# Center_Console_-_Buttons_Interface.net
KiCad netlist of a schematic drawn in Altium Designer
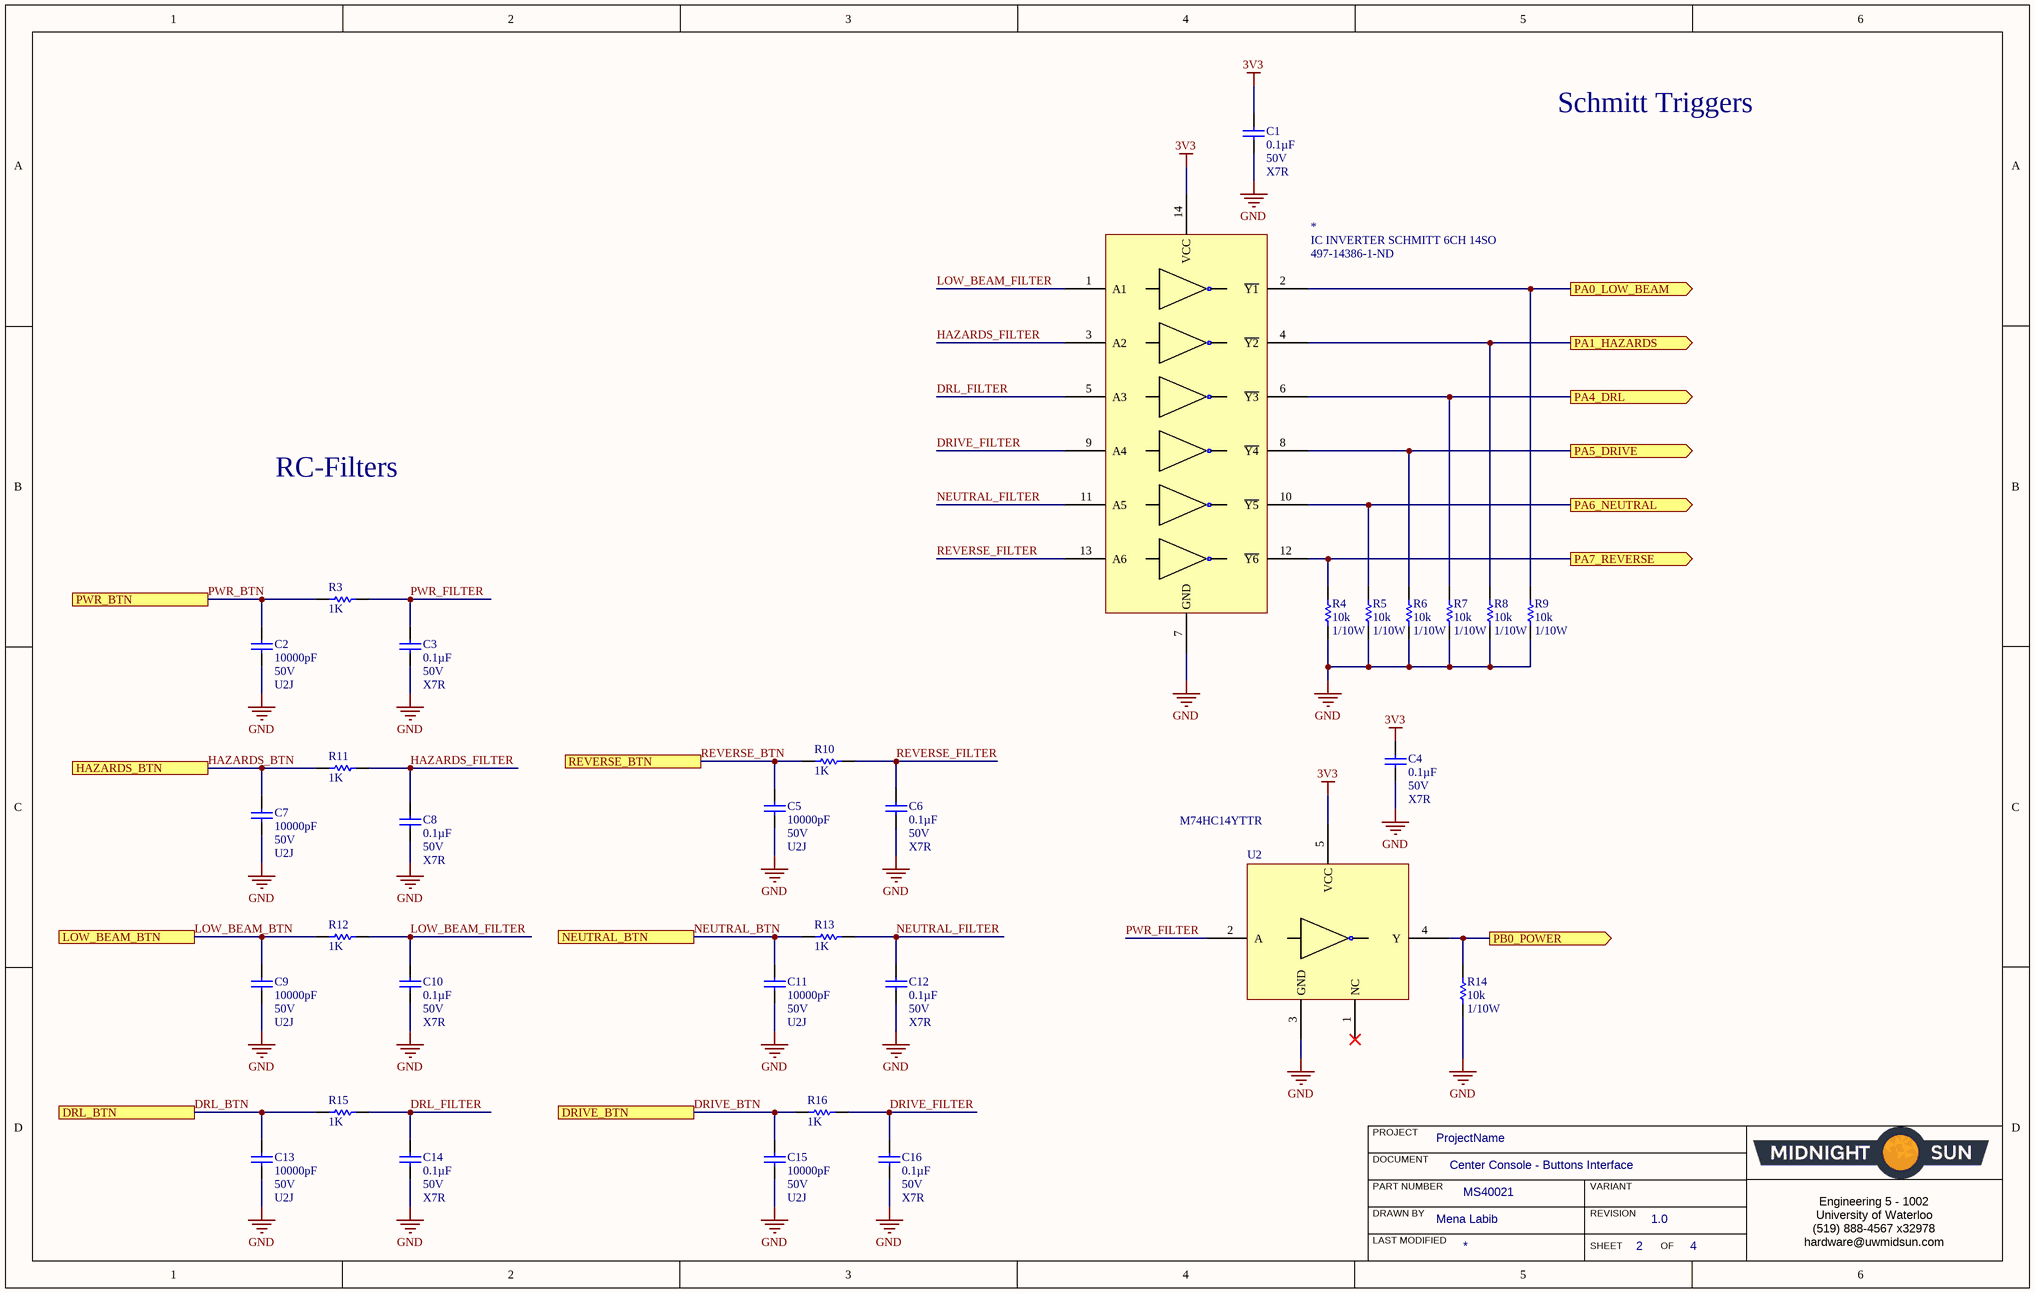
[diagram p0: Center Console - Buttons Interface.SchDoc]

(export (version "E")
  (design (tool "Eeschema 10.0.6"))
  (components
    (comp (ref "*")
      (value "IC INVERTER SCHMITT 6CH 14SO")
      (footprint "IC INVERTER SCHMITT 6CH 14TSO")
      (description "Inverter IC 6 Channel Schmitt Trigger 14-SO")
      (fields
        (field (name "MANUFACTURER") "STMicroelectronics")
        (field (name "MANUFACTURER PART NUMBER") "M74HC14YTTR")
        (field (name "SUPPLIER PART NUMBER 1") "497-14386-1-ND")
      )
      (libsource (lib "Schematic Diagrams") (part "IC INVERTER SCHMITT 6CH 14SO"))
    )
    (comp (ref "C1")
      (value "CAP CER 0.1UF 50V 10% X7R 0603")
      (footprint "CAP, 0603")
      (description "0.10µF ±10% 50V Ceramic Capacitor X7R 0603 (1608 Metric)")
      (fields
        (field (name "TOLERANCE") "±10%")
        (field (name "CAPACITANCE") "0.1µF")
        (field (name "VOLTAGE") "50V")
        (field (name "TEMPERATURE COEFFICIENT") "X7R")
      )
      (libsource (lib "Schematic Diagrams") (part "CAP CER 0.1UF 50V 10% X7R 0603"))
    )
    (comp (ref "C2")
      (value "CAP CER 10nF 50V 5% X7R 0603")
      (footprint "CAP, 0603")
      (description "10000pF ±5% 50V Ceramic Capacitor U2J 0603 (1608 Metric)")
      (fields
        (field (name "TOLERANCE") "±5%")
        (field (name "CAPACITANCE") "10000pF")
        (field (name "VOLTAGE") "50V")
        (field (name "TEMPERATURE COEFFICIENT") "U2J")
      )
      (libsource (lib "altium-import") (part "root_0_CAP CER 10nF 50V 5% X7R 0603_"))
    )
    (comp (ref "C3")
      (value "CAP CER 0.1UF 50V 10% X7R 0603")
      (footprint "CAP, 0603")
      (description "0.10µF ±10% 50V Ceramic Capacitor X7R 0603 (1608 Metric)")
      (fields
        (field (name "TOLERANCE") "±10%")
        (field (name "CAPACITANCE") "0.1µF")
        (field (name "VOLTAGE") "50V")
        (field (name "TEMPERATURE COEFFICIENT") "X7R")
      )
      (libsource (lib "Schematic Diagrams") (part "CAP CER 0.1UF 50V 10% X7R 0603"))
    )
    (comp (ref "C4")
      (value "CAP CER 0.1UF 50V 10% X7R 0603")
      (footprint "CAP, 0603")
      (description "0.10µF ±10% 50V Ceramic Capacitor X7R 0603 (1608 Metric)")
      (fields
        (field (name "TOLERANCE") "±10%")
        (field (name "CAPACITANCE") "0.1µF")
        (field (name "VOLTAGE") "50V")
        (field (name "TEMPERATURE COEFFICIENT") "X7R")
      )
      (libsource (lib "Schematic Diagrams") (part "CAP CER 0.1UF 50V 10% X7R 0603"))
    )
    (comp (ref "C5")
      (value "CAP CER 10nF 50V 5% X7R 0603")
      (footprint "CAP, 0603")
      (description "10000pF ±5% 50V Ceramic Capacitor U2J 0603 (1608 Metric)")
      (fields
        (field (name "TOLERANCE") "±5%")
        (field (name "CAPACITANCE") "10000pF")
        (field (name "VOLTAGE") "50V")
        (field (name "TEMPERATURE COEFFICIENT") "U2J")
      )
      (libsource (lib "altium-import") (part "root_0_CAP CER 10nF 50V 5% X7R 0603_"))
    )
    (comp (ref "C6")
      (value "CAP CER 0.1UF 50V 10% X7R 0603")
      (footprint "CAP, 0603")
      (description "0.10µF ±10% 50V Ceramic Capacitor X7R 0603 (1608 Metric)")
      (fields
        (field (name "TOLERANCE") "±10%")
        (field (name "CAPACITANCE") "0.1µF")
        (field (name "VOLTAGE") "50V")
        (field (name "TEMPERATURE COEFFICIENT") "X7R")
      )
      (libsource (lib "Schematic Diagrams") (part "CAP CER 0.1UF 50V 10% X7R 0603"))
    )
    (comp (ref "C7")
      (value "CAP CER 10nF 50V 5% X7R 0603")
      (footprint "CAP, 0603")
      (description "10000pF ±5% 50V Ceramic Capacitor U2J 0603 (1608 Metric)")
      (fields
        (field (name "TOLERANCE") "±5%")
        (field (name "CAPACITANCE") "10000pF")
        (field (name "VOLTAGE") "50V")
        (field (name "TEMPERATURE COEFFICIENT") "U2J")
      )
      (libsource (lib "altium-import") (part "root_0_CAP CER 10nF 50V 5% X7R 0603_"))
    )
    (comp (ref "C8")
      (value "CAP CER 0.1UF 50V 10% X7R 0603")
      (footprint "CAP, 0603")
      (description "0.10µF ±10% 50V Ceramic Capacitor X7R 0603 (1608 Metric)")
      (fields
        (field (name "TOLERANCE") "±10%")
        (field (name "CAPACITANCE") "0.1µF")
        (field (name "VOLTAGE") "50V")
        (field (name "TEMPERATURE COEFFICIENT") "X7R")
      )
      (libsource (lib "Schematic Diagrams") (part "CAP CER 0.1UF 50V 10% X7R 0603"))
    )
    (comp (ref "C9")
      (value "CAP CER 10nF 50V 5% X7R 0603")
      (footprint "CAP, 0603")
      (description "10000pF ±5% 50V Ceramic Capacitor U2J 0603 (1608 Metric)")
      (fields
        (field (name "TOLERANCE") "±5%")
        (field (name "CAPACITANCE") "10000pF")
        (field (name "VOLTAGE") "50V")
        (field (name "TEMPERATURE COEFFICIENT") "U2J")
      )
      (libsource (lib "altium-import") (part "root_0_CAP CER 10nF 50V 5% X7R 0603_"))
    )
    (comp (ref "C10")
      (value "CAP CER 0.1UF 50V 10% X7R 0603")
      (footprint "CAP, 0603")
      (description "0.10µF ±10% 50V Ceramic Capacitor X7R 0603 (1608 Metric)")
      (fields
        (field (name "TOLERANCE") "±10%")
        (field (name "CAPACITANCE") "0.1µF")
        (field (name "VOLTAGE") "50V")
        (field (name "TEMPERATURE COEFFICIENT") "X7R")
      )
      (libsource (lib "Schematic Diagrams") (part "CAP CER 0.1UF 50V 10% X7R 0603"))
    )
    (comp (ref "C11")
      (value "CAP CER 10nF 50V 5% X7R 0603")
      (footprint "CAP, 0603")
      (description "10000pF ±5% 50V Ceramic Capacitor U2J 0603 (1608 Metric)")
      (fields
        (field (name "TOLERANCE") "±5%")
        (field (name "CAPACITANCE") "10000pF")
        (field (name "VOLTAGE") "50V")
        (field (name "TEMPERATURE COEFFICIENT") "U2J")
      )
      (libsource (lib "altium-import") (part "root_0_CAP CER 10nF 50V 5% X7R 0603_"))
    )
    (comp (ref "C12")
      (value "CAP CER 0.1UF 50V 10% X7R 0603")
      (footprint "CAP, 0603")
      (description "0.10µF ±10% 50V Ceramic Capacitor X7R 0603 (1608 Metric)")
      (fields
        (field (name "TOLERANCE") "±10%")
        (field (name "CAPACITANCE") "0.1µF")
        (field (name "VOLTAGE") "50V")
        (field (name "TEMPERATURE COEFFICIENT") "X7R")
      )
      (libsource (lib "Schematic Diagrams") (part "CAP CER 0.1UF 50V 10% X7R 0603"))
    )
    (comp (ref "C13")
      (value "CAP CER 10nF 50V 5% X7R 0603")
      (footprint "CAP, 0603")
      (description "10000pF ±5% 50V Ceramic Capacitor U2J 0603 (1608 Metric)")
      (fields
        (field (name "TOLERANCE") "±5%")
        (field (name "CAPACITANCE") "10000pF")
        (field (name "VOLTAGE") "50V")
        (field (name "TEMPERATURE COEFFICIENT") "U2J")
      )
      (libsource (lib "altium-import") (part "root_0_CAP CER 10nF 50V 5% X7R 0603_"))
    )
    (comp (ref "C14")
      (value "CAP CER 0.1UF 50V 10% X7R 0603")
      (footprint "CAP, 0603")
      (description "0.10µF ±10% 50V Ceramic Capacitor X7R 0603 (1608 Metric)")
      (fields
        (field (name "TOLERANCE") "±10%")
        (field (name "CAPACITANCE") "0.1µF")
        (field (name "VOLTAGE") "50V")
        (field (name "TEMPERATURE COEFFICIENT") "X7R")
      )
      (libsource (lib "Schematic Diagrams") (part "CAP CER 0.1UF 50V 10% X7R 0603"))
    )
    (comp (ref "C15")
      (value "CAP CER 10nF 50V 5% X7R 0603")
      (footprint "CAP, 0603")
      (description "10000pF ±5% 50V Ceramic Capacitor U2J 0603 (1608 Metric)")
      (fields
        (field (name "TOLERANCE") "±5%")
        (field (name "CAPACITANCE") "10000pF")
        (field (name "VOLTAGE") "50V")
        (field (name "TEMPERATURE COEFFICIENT") "U2J")
      )
      (libsource (lib "altium-import") (part "root_0_CAP CER 10nF 50V 5% X7R 0603_"))
    )
    (comp (ref "C16")
      (value "CAP CER 0.1UF 50V 10% X7R 0603")
      (footprint "CAP, 0603")
      (description "0.10µF ±10% 50V Ceramic Capacitor X7R 0603 (1608 Metric)")
      (fields
        (field (name "TOLERANCE") "±10%")
        (field (name "CAPACITANCE") "0.1µF")
        (field (name "VOLTAGE") "50V")
        (field (name "TEMPERATURE COEFFICIENT") "X7R")
      )
      (libsource (lib "Schematic Diagrams") (part "CAP CER 0.1UF 50V 10% X7R 0603"))
    )
    (comp (ref "R3")
      (value "1K")
      (footprint "RES, 0603")
      (description "1k Ohm ±5% 0.1W, 1/10W Chip Resistor 0603 (1608 Metric)")
      (fields
        (field (name "MANUFACTURER") "Yageo")
        (field (name "MANUFACTURER PART NUMBER") "RC0603JR-071KL")
      )
      (libsource (lib "Schematic Diagrams") (part "RES 1K OHM 5% 1/10W 0603"))
    )
    (comp (ref "R4")
      (value "RES 10K OHM 1% 1/10W 0603")
      (footprint "RES, 0603")
      (description "RES SMD 10K OHM 1% 1/10W 0603")
      (fields
        (field (name "TOLERANCE") "±1%")
        (field (name "RESISTANCE") "10k")
        (field (name "POWER") "1/10W")
      )
      (libsource (lib "altium-import") (part "root_0_RES 10K OHM 1% 1/10W 0603_"))
    )
    (comp (ref "R5")
      (value "RES 10K OHM 1% 1/10W 0603")
      (footprint "RES, 0603")
      (description "RES SMD 10K OHM 1% 1/10W 0603")
      (fields
        (field (name "TOLERANCE") "±1%")
        (field (name "RESISTANCE") "10k")
        (field (name "POWER") "1/10W")
      )
      (libsource (lib "altium-import") (part "root_0_RES 10K OHM 1% 1/10W 0603_"))
    )
    (comp (ref "R6")
      (value "RES 10K OHM 1% 1/10W 0603")
      (footprint "RES, 0603")
      (description "RES SMD 10K OHM 1% 1/10W 0603")
      (fields
        (field (name "TOLERANCE") "±1%")
        (field (name "RESISTANCE") "10k")
        (field (name "POWER") "1/10W")
      )
      (libsource (lib "altium-import") (part "root_0_RES 10K OHM 1% 1/10W 0603_"))
    )
    (comp (ref "R7")
      (value "RES 10K OHM 1% 1/10W 0603")
      (footprint "RES, 0603")
      (description "RES SMD 10K OHM 1% 1/10W 0603")
      (fields
        (field (name "TOLERANCE") "±1%")
        (field (name "RESISTANCE") "10k")
        (field (name "POWER") "1/10W")
      )
      (libsource (lib "altium-import") (part "root_0_RES 10K OHM 1% 1/10W 0603_"))
    )
    (comp (ref "R8")
      (value "RES 10K OHM 1% 1/10W 0603")
      (footprint "RES, 0603")
      (description "RES SMD 10K OHM 1% 1/10W 0603")
      (fields
        (field (name "TOLERANCE") "±1%")
        (field (name "RESISTANCE") "10k")
        (field (name "POWER") "1/10W")
      )
      (libsource (lib "altium-import") (part "root_0_RES 10K OHM 1% 1/10W 0603_"))
    )
    (comp (ref "R9")
      (value "RES 10K OHM 1% 1/10W 0603")
      (footprint "RES, 0603")
      (description "RES SMD 10K OHM 1% 1/10W 0603")
      (fields
        (field (name "TOLERANCE") "±1%")
        (field (name "RESISTANCE") "10k")
        (field (name "POWER") "1/10W")
      )
      (libsource (lib "altium-import") (part "root_0_RES 10K OHM 1% 1/10W 0603_"))
    )
    (comp (ref "R10")
      (value "1K")
      (footprint "RES, 0603")
      (description "1k Ohm ±5% 0.1W, 1/10W Chip Resistor 0603 (1608 Metric)")
      (fields
        (field (name "MANUFACTURER") "Yageo")
        (field (name "MANUFACTURER PART NUMBER") "RC0603JR-071KL")
      )
      (libsource (lib "Schematic Diagrams") (part "RES 1K OHM 5% 1/10W 0603"))
    )
    (comp (ref "R11")
      (value "1K")
      (footprint "RES, 0603")
      (description "1k Ohm ±5% 0.1W, 1/10W Chip Resistor 0603 (1608 Metric)")
      (fields
        (field (name "MANUFACTURER") "Yageo")
        (field (name "MANUFACTURER PART NUMBER") "RC0603JR-071KL")
      )
      (libsource (lib "Schematic Diagrams") (part "RES 1K OHM 5% 1/10W 0603"))
    )
    (comp (ref "R12")
      (value "1K")
      (footprint "RES, 0603")
      (description "1k Ohm ±5% 0.1W, 1/10W Chip Resistor 0603 (1608 Metric)")
      (fields
        (field (name "MANUFACTURER") "Yageo")
        (field (name "MANUFACTURER PART NUMBER") "RC0603JR-071KL")
      )
      (libsource (lib "Schematic Diagrams") (part "RES 1K OHM 5% 1/10W 0603"))
    )
    (comp (ref "R13")
      (value "1K")
      (footprint "RES, 0603")
      (description "1k Ohm ±5% 0.1W, 1/10W Chip Resistor 0603 (1608 Metric)")
      (fields
        (field (name "MANUFACTURER") "Yageo")
        (field (name "MANUFACTURER PART NUMBER") "RC0603JR-071KL")
      )
      (libsource (lib "Schematic Diagrams") (part "RES 1K OHM 5% 1/10W 0603"))
    )
    (comp (ref "R14")
      (value "RES 10K OHM 1% 1/10W 0603")
      (footprint "RES, 0603")
      (description "RES SMD 10K OHM 1% 1/10W 0603")
      (fields
        (field (name "TOLERANCE") "±1%")
        (field (name "RESISTANCE") "10k")
        (field (name "POWER") "1/10W")
      )
      (libsource (lib "altium-import") (part "root_0_RES 10K OHM 1% 1/10W 0603_"))
    )
    (comp (ref "R15")
      (value "1K")
      (footprint "RES, 0603")
      (description "1k Ohm ±5% 0.1W, 1/10W Chip Resistor 0603 (1608 Metric)")
      (fields
        (field (name "MANUFACTURER") "Yageo")
        (field (name "MANUFACTURER PART NUMBER") "RC0603JR-071KL")
      )
      (libsource (lib "Schematic Diagrams") (part "RES 1K OHM 5% 1/10W 0603"))
    )
    (comp (ref "R16")
      (value "1K")
      (footprint "RES, 0603")
      (description "1k Ohm ±5% 0.1W, 1/10W Chip Resistor 0603 (1608 Metric)")
      (fields
        (field (name "MANUFACTURER") "Yageo")
        (field (name "MANUFACTURER PART NUMBER") "RC0603JR-071KL")
      )
      (libsource (lib "Schematic Diagrams") (part "RES 1K OHM 5% 1/10W 0603"))
    )
    (comp (ref "U2")
      (value "IC INVERTER SCHMITT 1CH SC70-5")
      (footprint "IC INVERTER SCHMITT 1CH SC70-5")
      (description "Inverter IC 1 Channel Schmitt Trigger SC-70-5")
      (fields
        (field (name "MANUFACTURER") "STMicroelectronics")
        (field (name "MANUFACTURER PART NUMBER") "M74HC14YTTR")
      )
      (libsource (lib "Schematic Diagrams") (part "IC INVERTER SCHMITT 1CH SC70-5"))
    )
  )
  (nets
    (net (code "1") (name "/DRIVE_BTN") (class "Default")
      (node (ref "C15") (pin "1") (pinfunction "1_1") (pintype "passive"))
      (node (ref "R16") (pin "1") (pinfunction "1_1") (pintype "passive"))
    )
    (net (code "2") (name "/DRIVE_FILTER") (class "Default")
      (node (ref "*") (pin "9") (pinfunction "A4_9") (pintype "passive"))
      (node (ref "C16") (pin "1") (pinfunction "1_1") (pintype "passive"))
      (node (ref "R16") (pin "2") (pinfunction "2_2") (pintype "passive"))
    )
    (net (code "3") (name "/DRL_BTN") (class "Default")
      (node (ref "C13") (pin "1") (pinfunction "1_1") (pintype "passive"))
      (node (ref "R15") (pin "1") (pinfunction "1_1") (pintype "passive"))
    )
    (net (code "4") (name "/DRL_FILTER") (class "Default")
      (node (ref "*") (pin "5") (pinfunction "A3_5") (pintype "passive"))
      (node (ref "C14") (pin "1") (pinfunction "1_1") (pintype "passive"))
      (node (ref "R15") (pin "2") (pinfunction "2_2") (pintype "passive"))
    )
    (net (code "5") (name "/HAZARDS_BTN") (class "Default")
      (node (ref "C7") (pin "1") (pinfunction "1_1") (pintype "passive"))
      (node (ref "R11") (pin "1") (pinfunction "1_1") (pintype "passive"))
    )
    (net (code "6") (name "/HAZARDS_FILTER") (class "Default")
      (node (ref "*") (pin "3") (pinfunction "A2_3") (pintype "passive"))
      (node (ref "C8") (pin "1") (pinfunction "1_1") (pintype "passive"))
      (node (ref "R11") (pin "2") (pinfunction "2_2") (pintype "passive"))
    )
    (net (code "7") (name "/LOW_BEAM_BTN") (class "Default")
      (node (ref "C9") (pin "1") (pinfunction "1_1") (pintype "passive"))
      (node (ref "R12") (pin "1") (pinfunction "1_1") (pintype "passive"))
    )
    (net (code "8") (name "/LOW_BEAM_FILTER") (class "Default")
      (node (ref "*") (pin "1") (pinfunction "A1_1") (pintype "passive"))
      (node (ref "C10") (pin "1") (pinfunction "1_1") (pintype "passive"))
      (node (ref "R12") (pin "2") (pinfunction "2_2") (pintype "passive"))
    )
    (net (code "9") (name "/NEUTRAL_BTN") (class "Default")
      (node (ref "C11") (pin "1") (pinfunction "1_1") (pintype "passive"))
      (node (ref "R13") (pin "1") (pinfunction "1_1") (pintype "passive"))
    )
    (net (code "10") (name "/NEUTRAL_FILTER") (class "Default")
      (node (ref "*") (pin "11") (pinfunction "A5_11") (pintype "passive"))
      (node (ref "C12") (pin "1") (pinfunction "1_1") (pintype "passive"))
      (node (ref "R13") (pin "2") (pinfunction "2_2") (pintype "passive"))
    )
    (net (code "11") (name "/PA0_LOW_BEAM") (class "Default")
      (node (ref "*") (pin "2") (pinfunction "~{Y1}_2") (pintype "passive"))
      (node (ref "R9") (pin "1") (pinfunction "1_1") (pintype "passive"))
    )
    (net (code "12") (name "/PA1_HAZARDS") (class "Default")
      (node (ref "*") (pin "4") (pinfunction "~{Y2}_4") (pintype "passive"))
      (node (ref "R8") (pin "1") (pinfunction "1_1") (pintype "passive"))
    )
    (net (code "13") (name "/PA4_DRL") (class "Default")
      (node (ref "*") (pin "6") (pinfunction "~{Y3}_6") (pintype "passive"))
      (node (ref "R7") (pin "1") (pinfunction "1_1") (pintype "passive"))
    )
    (net (code "14") (name "/PA5_DRIVE") (class "Default")
      (node (ref "*") (pin "8") (pinfunction "~{Y4}_8") (pintype "passive"))
      (node (ref "R6") (pin "1") (pinfunction "1_1") (pintype "passive"))
    )
    (net (code "15") (name "/PA6_NEUTRAL") (class "Default")
      (node (ref "*") (pin "10") (pinfunction "~{Y5}_10") (pintype "passive"))
      (node (ref "R5") (pin "1") (pinfunction "1_1") (pintype "passive"))
    )
    (net (code "16") (name "/PA7_REVERSE") (class "Default")
      (node (ref "*") (pin "12") (pinfunction "~{Y6}_12") (pintype "passive"))
      (node (ref "R4") (pin "1") (pinfunction "1_1") (pintype "passive"))
    )
    (net (code "17") (name "/PB0_POWER") (class "Default")
      (node (ref "R14") (pin "1") (pinfunction "1_1") (pintype "passive"))
      (node (ref "U2") (pin "4") (pinfunction "Y_4") (pintype "passive"))
    )
    (net (code "18") (name "/PWR_BTN") (class "Default")
      (node (ref "C2") (pin "1") (pinfunction "1_1") (pintype "passive"))
      (node (ref "R3") (pin "1") (pinfunction "1_1") (pintype "passive"))
    )
    (net (code "19") (name "/PWR_FILTER") (class "Default")
      (node (ref "C3") (pin "1") (pinfunction "1_1") (pintype "passive"))
      (node (ref "R3") (pin "2") (pinfunction "2_2") (pintype "passive"))
      (node (ref "U2") (pin "2") (pinfunction "A_2") (pintype "passive"))
    )
    (net (code "20") (name "/REVERSE_BTN") (class "Default")
      (node (ref "C5") (pin "1") (pinfunction "1_1") (pintype "passive"))
      (node (ref "R10") (pin "1") (pinfunction "1_1") (pintype "passive"))
    )
    (net (code "21") (name "/REVERSE_FILTER") (class "Default")
      (node (ref "*") (pin "13") (pinfunction "A6_13") (pintype "passive"))
      (node (ref "C6") (pin "1") (pinfunction "1_1") (pintype "passive"))
      (node (ref "R10") (pin "2") (pinfunction "2_2") (pintype "passive"))
    )
    (net (code "22") (name "3V3") (class "Default")
      (node (ref "*") (pin "14") (pinfunction "VCC_14") (pintype "passive"))
      (node (ref "C1") (pin "1") (pinfunction "1_1") (pintype "passive"))
      (node (ref "C4") (pin "1") (pinfunction "1_1") (pintype "passive"))
      (node (ref "U2") (pin "5") (pinfunction "VCC_5") (pintype "passive"))
    )
    (net (code "23") (name "GND") (class "Default")
      (node (ref "*") (pin "7") (pinfunction "GND_7") (pintype "passive"))
      (node (ref "C1") (pin "2") (pinfunction "2_2") (pintype "passive"))
      (node (ref "C10") (pin "2") (pinfunction "2_2") (pintype "passive"))
      (node (ref "C11") (pin "2") (pinfunction "2_2") (pintype "passive"))
      (node (ref "C12") (pin "2") (pinfunction "2_2") (pintype "passive"))
      (node (ref "C13") (pin "2") (pinfunction "2_2") (pintype "passive"))
      (node (ref "C14") (pin "2") (pinfunction "2_2") (pintype "passive"))
      (node (ref "C15") (pin "2") (pinfunction "2_2") (pintype "passive"))
      (node (ref "C16") (pin "2") (pinfunction "2_2") (pintype "passive"))
      (node (ref "C2") (pin "2") (pinfunction "2_2") (pintype "passive"))
      (node (ref "C3") (pin "2") (pinfunction "2_2") (pintype "passive"))
      (node (ref "C4") (pin "2") (pinfunction "2_2") (pintype "passive"))
      (node (ref "C5") (pin "2") (pinfunction "2_2") (pintype "passive"))
      (node (ref "C6") (pin "2") (pinfunction "2_2") (pintype "passive"))
      (node (ref "C7") (pin "2") (pinfunction "2_2") (pintype "passive"))
      (node (ref "C8") (pin "2") (pinfunction "2_2") (pintype "passive"))
      (node (ref "C9") (pin "2") (pinfunction "2_2") (pintype "passive"))
      (node (ref "R14") (pin "2") (pinfunction "2_2") (pintype "passive"))
      (node (ref "R4") (pin "2") (pinfunction "2_2") (pintype "passive"))
      (node (ref "R5") (pin "2") (pinfunction "2_2") (pintype "passive"))
      (node (ref "R6") (pin "2") (pinfunction "2_2") (pintype "passive"))
      (node (ref "R7") (pin "2") (pinfunction "2_2") (pintype "passive"))
      (node (ref "R8") (pin "2") (pinfunction "2_2") (pintype "passive"))
      (node (ref "R9") (pin "2") (pinfunction "2_2") (pintype "passive"))
      (node (ref "U2") (pin "3") (pinfunction "GND_3") (pintype "passive"))
    )
    (net (code "24") (name "unconnected-(U2-NC-Pad1)") (class "Default")
      (node (ref "U2") (pin "1") (pinfunction "NC_1") (pintype "passive+no_connect"))
    )
  )
)
